# 1-Schematic_RUBBER_DUCKY.net
KiCad netlist of a schematic drawn in EasyEDA
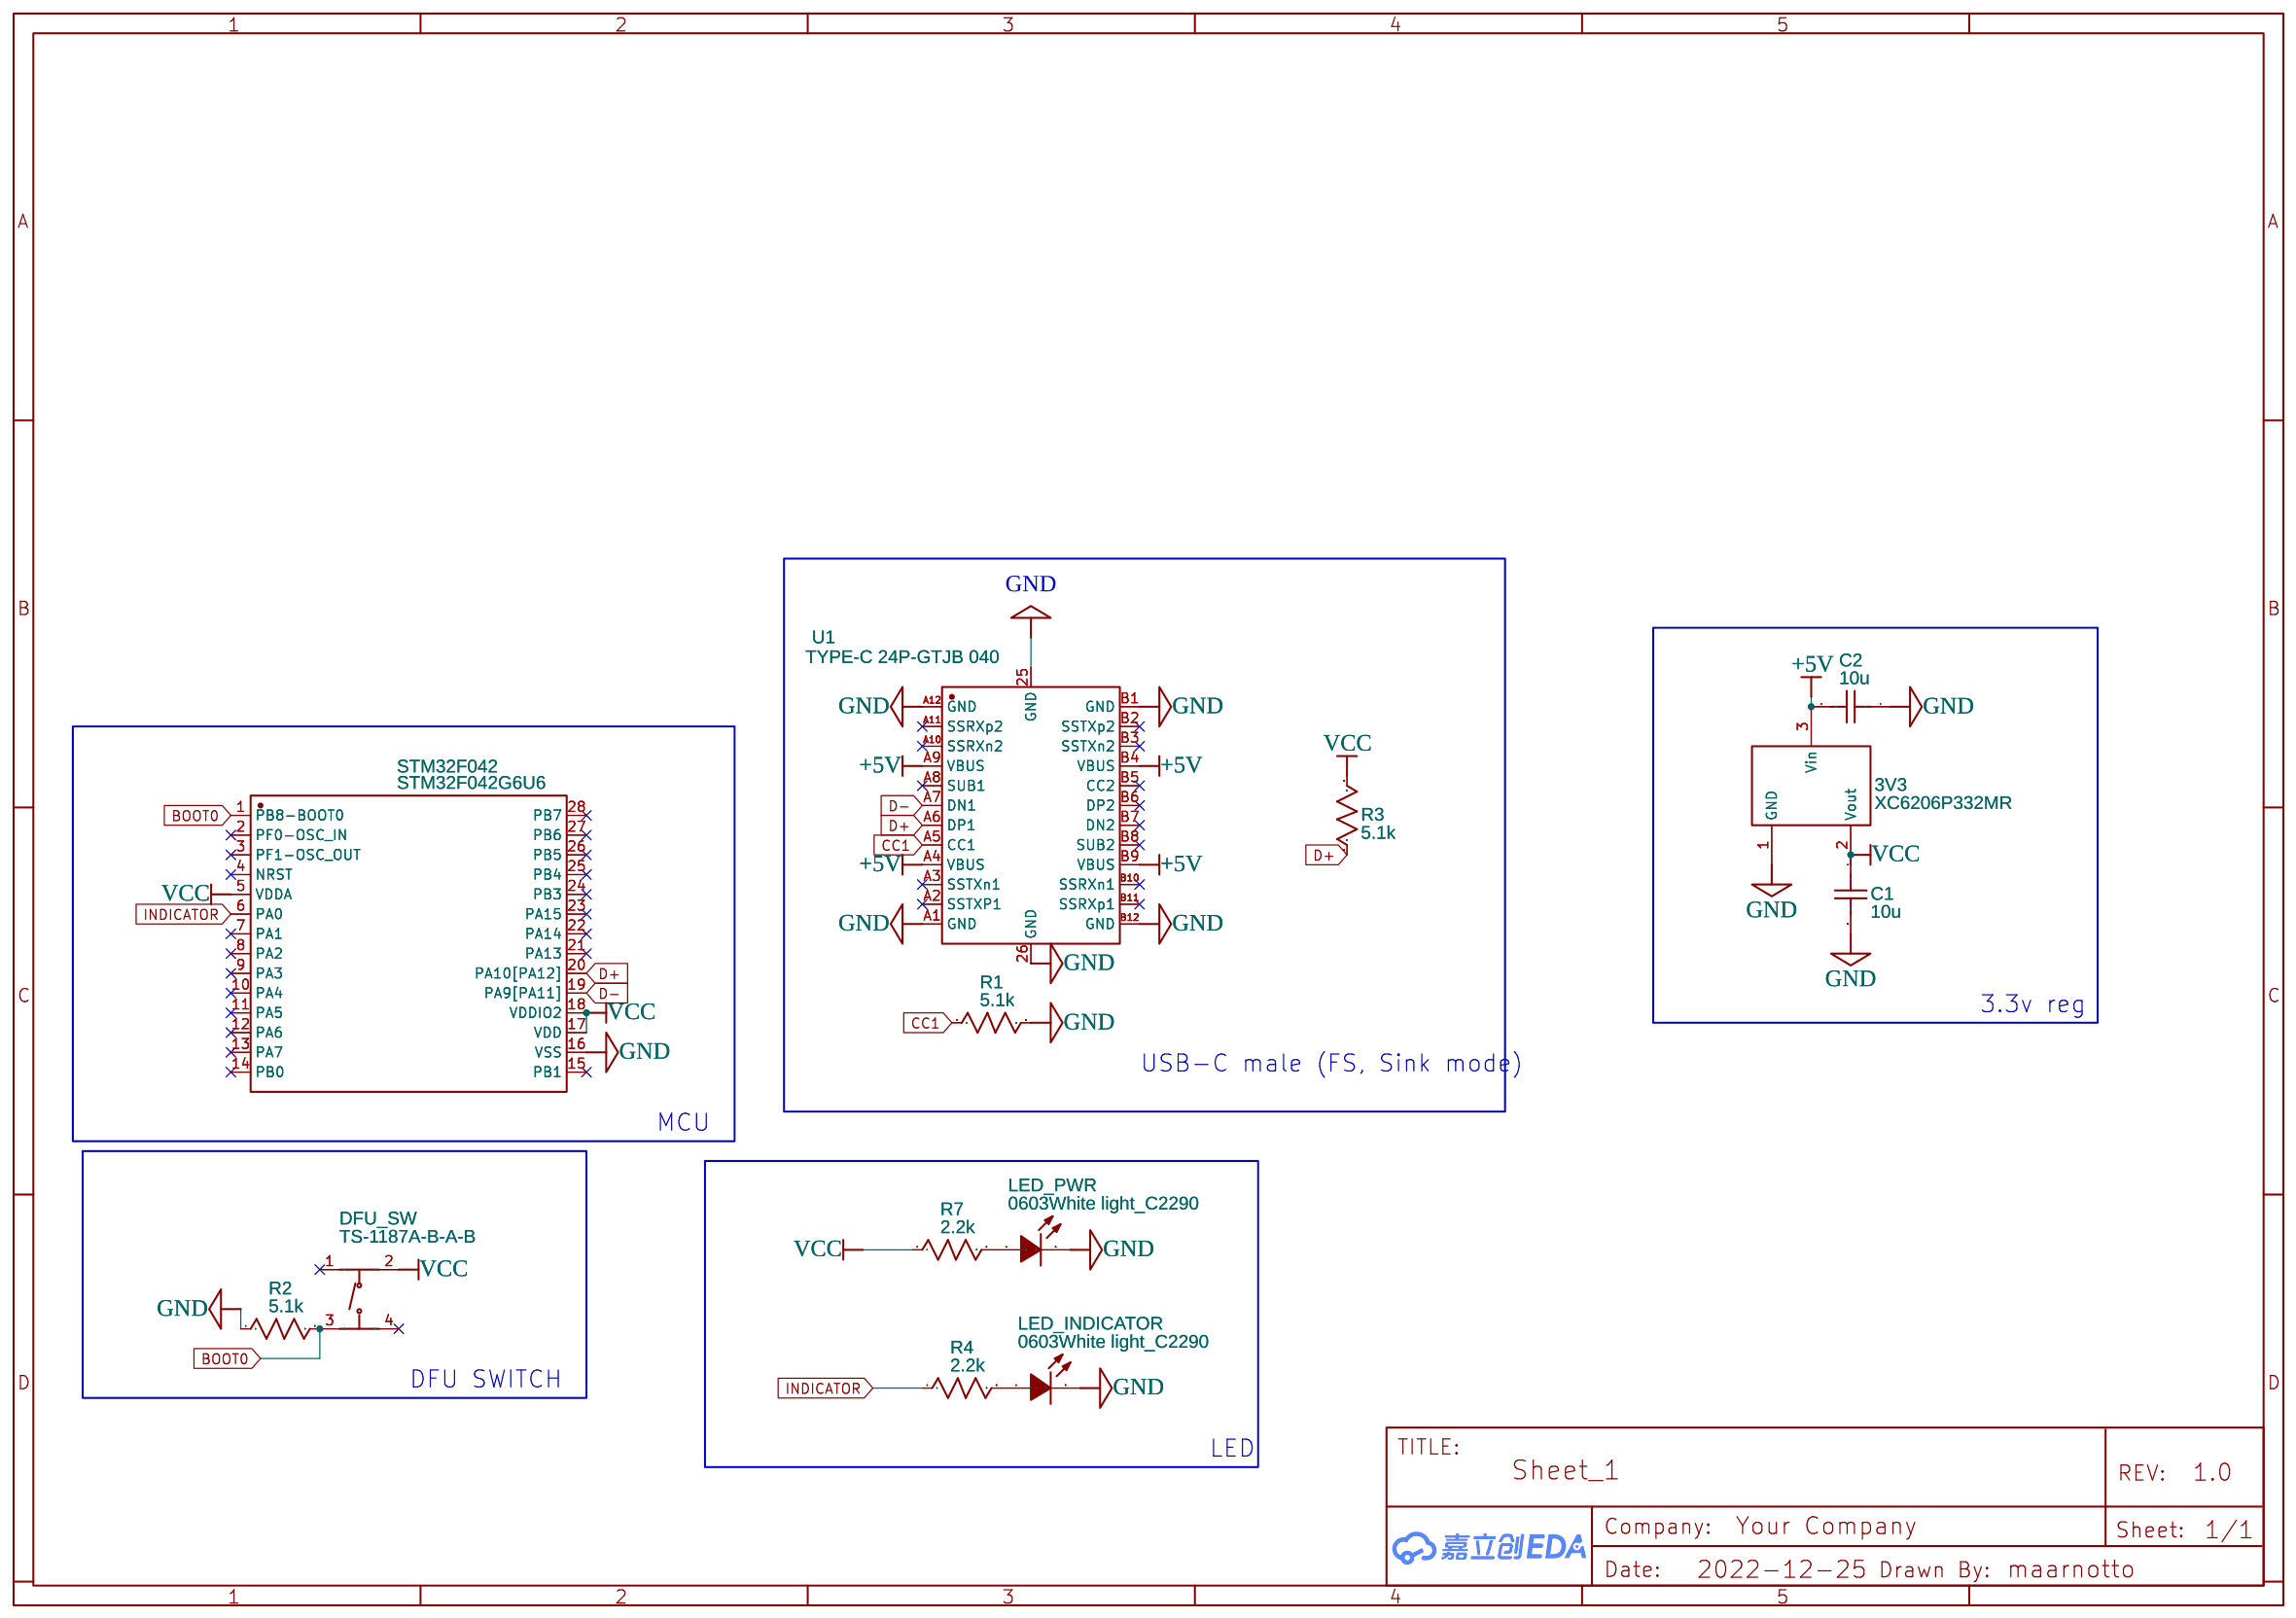
[diagram p0: schematic sheet]

(export (version "E")
  (design (tool "Eeschema 10.0.6"))
  (components
    (comp (ref "3V3")
      (value "XC6206P332MR")
      (fields (field (name "Manufacturer") "TOREX(特瑞仕)"))
      (libsource (lib "") (part "XC6206P332MR"))
    )
    (comp (ref "C1") (value "10u") (libsource (lib "") (part "C_0603_US_1")))
    (comp (ref "C2") (value "10u") (libsource (lib "") (part "C_0603_US")))
    (comp (ref "DFU_SW")
      (value "TS-1187A-B-A-B")
      (fields (field (name "Manufacturer") "XKB Connectivity(中国星坤)"))
      (libsource (lib "") (part "TS-1187A-B-A-B"))
    )
    (comp (ref "LED_INDICATOR")
      (value "0603White light_C2290")
      (fields (field (name "Manufacturer Part") "KT-0603白灯"))
      (libsource (lib "") (part "0603White light_C2290"))
    )
    (comp (ref "LED_PWR")
      (value "0603White light_C2290")
      (fields (field (name "Manufacturer Part") "KT-0603白灯"))
      (libsource (lib "") (part "0603White light_C2290_1"))
    )
    (comp (ref "R1") (value "5.1k") (libsource (lib "") (part "R_0603_US")))
    (comp (ref "R2") (value "5.1k") (libsource (lib "") (part "R_0603_US")))
    (comp (ref "R3") (value "5.1k") (libsource (lib "") (part "R_0603_US_1")))
    (comp (ref "R4") (value "2.2k") (libsource (lib "") (part "R_0603_US")))
    (comp (ref "R7") (value "2.2k") (libsource (lib "") (part "R_0603_US")))
    (comp (ref "STM32F042")
      (value "STM32F042G6U6")
      (fields (field (name "Manufacturer") "ST(意法半导体)"))
      (libsource (lib "") (part "STM32F042G6U6"))
    )
    (comp (ref "U1")
      (value "TYPE-C 24P-GTJB 040")
      (fields (field (name "Manufacturer") "SHOU HAN(首韩)"))
      (libsource (lib "") (part "TYPE-C 24P-GTJB 040"))
    )
  )
  (nets
    (net (code "1") (name "+5V") (class "Default")
      (node (ref "3V3") (pin "3") (pinfunction "Vin_3") (pintype "unspecified"))
      (node (ref "C2") (pin "2") (pinfunction "2_2") (pintype "unspecified"))
      (node (ref "U1") (pin "A4") (pinfunction "VBUS_A4") (pintype "unspecified"))
      (node (ref "U1") (pin "A9") (pinfunction "VBUS_A9") (pintype "unspecified"))
      (node (ref "U1") (pin "B4") (pinfunction "VBUS_B4") (pintype "unspecified"))
      (node (ref "U1") (pin "B9") (pinfunction "VBUS_B9") (pintype "unspecified"))
    )
    (net (code "2") (name "BOOT0") (class "Default")
      (node (ref "DFU_SW") (pin "3") (pinfunction "C_3") (pintype "unspecified"))
      (node (ref "R2") (pin "2") (pinfunction "2_2") (pintype "unspecified"))
      (node (ref "STM32F042") (pin "1") (pinfunction "PB8-BOOT0_1") (pintype "unspecified"))
    )
    (net (code "3") (name "CC1") (class "Default")
      (node (ref "R1") (pin "1") (pinfunction "1_1") (pintype "unspecified"))
      (node (ref "U1") (pin "A5") (pinfunction "CC1_A5") (pintype "unspecified"))
    )
    (net (code "4") (name "D+") (class "Default")
      (node (ref "R3") (pin "2") (pinfunction "2_2") (pintype "unspecified"))
      (node (ref "STM32F042") (pin "20") (pinfunction "PA10[PA12]_20") (pintype "unspecified"))
      (node (ref "U1") (pin "A6") (pinfunction "DP1_A6") (pintype "unspecified"))
    )
    (net (code "5") (name "D-") (class "Default")
      (node (ref "STM32F042") (pin "19") (pinfunction "PA9[PA11]_19") (pintype "unspecified"))
      (node (ref "U1") (pin "A7") (pinfunction "DN1_A7") (pintype "unspecified"))
    )
    (net (code "6") (name "GND") (class "Default")
      (node (ref "3V3") (pin "1") (pinfunction "GND_1") (pintype "unspecified"))
      (node (ref "C1") (pin "2") (pinfunction "2_2") (pintype "unspecified"))
      (node (ref "C2") (pin "1") (pinfunction "1_1") (pintype "unspecified"))
      (node (ref "LED_INDICATOR") (pin "2") (pinfunction "K_2") (pintype "unspecified"))
      (node (ref "LED_PWR") (pin "2") (pinfunction "K_2") (pintype "unspecified"))
      (node (ref "R1") (pin "2") (pinfunction "2_2") (pintype "unspecified"))
      (node (ref "R2") (pin "1") (pinfunction "1_1") (pintype "unspecified"))
      (node (ref "STM32F042") (pin "16") (pinfunction "VSS_16") (pintype "unspecified"))
      (node (ref "U1") (pin "25") (pinfunction "GND_25") (pintype "unspecified"))
      (node (ref "U1") (pin "26") (pinfunction "GND_26") (pintype "unspecified"))
      (node (ref "U1") (pin "A1") (pinfunction "GND_A1") (pintype "unspecified"))
      (node (ref "U1") (pin "A12") (pinfunction "GND_A12") (pintype "unspecified"))
      (node (ref "U1") (pin "B1") (pinfunction "GND_B1") (pintype "unspecified"))
      (node (ref "U1") (pin "B12") (pinfunction "GND_B12") (pintype "unspecified"))
    )
    (net (code "7") (name "INDICATOR") (class "Default")
      (node (ref "R4") (pin "1") (pinfunction "1_1") (pintype "unspecified"))
      (node (ref "STM32F042") (pin "6") (pinfunction "PA0_6") (pintype "unspecified"))
    )
    (net (code "8") (name "Net-(LED_INDICATOR-A)") (class "Default")
      (node (ref "LED_INDICATOR") (pin "1") (pinfunction "A_1") (pintype "unspecified"))
      (node (ref "R4") (pin "2") (pinfunction "2_2") (pintype "unspecified"))
    )
    (net (code "9") (name "Net-(LED_PWR-A)") (class "Default")
      (node (ref "LED_PWR") (pin "1") (pinfunction "A_1") (pintype "unspecified"))
      (node (ref "R7") (pin "2") (pinfunction "2_2") (pintype "unspecified"))
    )
    (net (code "10") (name "VCC") (class "Default")
      (node (ref "3V3") (pin "2") (pinfunction "Vout_2") (pintype "unspecified"))
      (node (ref "C1") (pin "1") (pinfunction "1_1") (pintype "unspecified"))
      (node (ref "DFU_SW") (pin "2") (pinfunction "B_2") (pintype "unspecified"))
      (node (ref "R3") (pin "1") (pinfunction "1_1") (pintype "unspecified"))
      (node (ref "R7") (pin "1") (pinfunction "1_1") (pintype "unspecified"))
      (node (ref "STM32F042") (pin "17") (pinfunction "VDD_17") (pintype "unspecified"))
      (node (ref "STM32F042") (pin "18") (pinfunction "VDDIO2_18") (pintype "unspecified"))
      (node (ref "STM32F042") (pin "5") (pinfunction "VDDA_5") (pintype "unspecified"))
    )
    (net (code "11") (name "unconnected-(DFU_SW-A-Pad1)") (class "Default")
      (node (ref "DFU_SW") (pin "1") (pinfunction "A_1") (pintype "unspecified+no_connect"))
    )
    (net (code "12") (name "unconnected-(DFU_SW-D-Pad4)") (class "Default")
      (node (ref "DFU_SW") (pin "4") (pinfunction "D_4") (pintype "unspecified+no_connect"))
    )
    (net (code "13") (name "unconnected-(STM32F042-NRST-Pad4)") (class "Default")
      (node (ref "STM32F042") (pin "4") (pinfunction "NRST_4") (pintype "unspecified+no_connect"))
    )
    (net (code "14") (name "unconnected-(STM32F042-PA1-Pad7)") (class "Default")
      (node (ref "STM32F042") (pin "7") (pinfunction "PA1_7") (pintype "unspecified+no_connect"))
    )
    (net (code "15") (name "unconnected-(STM32F042-PA2-Pad8)") (class "Default")
      (node (ref "STM32F042") (pin "8") (pinfunction "PA2_8") (pintype "unspecified+no_connect"))
    )
    (net (code "16") (name "unconnected-(STM32F042-PA3-Pad9)") (class "Default")
      (node (ref "STM32F042") (pin "9") (pinfunction "PA3_9") (pintype "unspecified+no_connect"))
    )
    (net (code "17") (name "unconnected-(STM32F042-PA4-Pad10)") (class "Default")
      (node (ref "STM32F042") (pin "10") (pinfunction "PA4_10") (pintype "unspecified+no_connect"))
    )
    (net (code "18") (name "unconnected-(STM32F042-PA5-Pad11)") (class "Default")
      (node (ref "STM32F042") (pin "11") (pinfunction "PA5_11") (pintype "unspecified+no_connect"))
    )
    (net (code "19") (name "unconnected-(STM32F042-PA6-Pad12)") (class "Default")
      (node (ref "STM32F042") (pin "12") (pinfunction "PA6_12") (pintype "unspecified+no_connect"))
    )
    (net (code "20") (name "unconnected-(STM32F042-PA7-Pad13)") (class "Default")
      (node (ref "STM32F042") (pin "13") (pinfunction "PA7_13") (pintype "unspecified+no_connect"))
    )
    (net (code "21") (name "unconnected-(STM32F042-PA13-Pad21)") (class "Default")
      (node (ref "STM32F042") (pin "21") (pinfunction "PA13_21") (pintype "unspecified+no_connect"))
    )
    (net (code "22") (name "unconnected-(STM32F042-PA14-Pad22)") (class "Default")
      (node (ref "STM32F042") (pin "22") (pinfunction "PA14_22") (pintype "unspecified+no_connect"))
    )
    (net (code "23") (name "unconnected-(STM32F042-PA15-Pad23)") (class "Default")
      (node (ref "STM32F042") (pin "23") (pinfunction "PA15_23") (pintype "unspecified+no_connect"))
    )
    (net (code "24") (name "unconnected-(STM32F042-PB0-Pad14)") (class "Default")
      (node (ref "STM32F042") (pin "14") (pinfunction "PB0_14") (pintype "unspecified+no_connect"))
    )
    (net (code "25") (name "unconnected-(STM32F042-PB1-Pad15)") (class "Default")
      (node (ref "STM32F042") (pin "15") (pinfunction "PB1_15") (pintype "unspecified+no_connect"))
    )
    (net (code "26") (name "unconnected-(STM32F042-PB3-Pad24)") (class "Default")
      (node (ref "STM32F042") (pin "24") (pinfunction "PB3_24") (pintype "unspecified+no_connect"))
    )
    (net (code "27") (name "unconnected-(STM32F042-PB4-Pad25)") (class "Default")
      (node (ref "STM32F042") (pin "25") (pinfunction "PB4_25") (pintype "unspecified+no_connect"))
    )
    (net (code "28") (name "unconnected-(STM32F042-PB5-Pad26)") (class "Default")
      (node (ref "STM32F042") (pin "26") (pinfunction "PB5_26") (pintype "unspecified+no_connect"))
    )
    (net (code "29") (name "unconnected-(STM32F042-PB6-Pad27)") (class "Default")
      (node (ref "STM32F042") (pin "27") (pinfunction "PB6_27") (pintype "unspecified+no_connect"))
    )
    (net (code "30") (name "unconnected-(STM32F042-PB7-Pad28)") (class "Default")
      (node (ref "STM32F042") (pin "28") (pinfunction "PB7_28") (pintype "unspecified+no_connect"))
    )
    (net (code "31") (name "unconnected-(STM32F042-PF0-OSC_IN-Pad2)") (class "Default")
      (node (ref "STM32F042") (pin "2") (pinfunction "PF0-OSC_IN_2") (pintype "unspecified+no_connect"))
    )
    (net (code "32") (name "unconnected-(STM32F042-PF1-OSC_OUT-Pad3)") (class "Default")
      (node (ref "STM32F042") (pin "3") (pinfunction "PF1-OSC_OUT_3") (pintype "unspecified+no_connect"))
    )
    (net (code "33") (name "unconnected-(U1-CC2-PadB5)") (class "Default")
      (node (ref "U1") (pin "B5") (pinfunction "CC2_B5") (pintype "unspecified+no_connect"))
    )
    (net (code "34") (name "unconnected-(U1-DN2-PadB7)") (class "Default")
      (node (ref "U1") (pin "B7") (pinfunction "DN2_B7") (pintype "unspecified+no_connect"))
    )
    (net (code "35") (name "unconnected-(U1-DP2-PadB6)") (class "Default")
      (node (ref "U1") (pin "B6") (pinfunction "DP2_B6") (pintype "unspecified+no_connect"))
    )
    (net (code "36") (name "unconnected-(U1-SSRXn1-PadB10)") (class "Default")
      (node (ref "U1") (pin "B10") (pinfunction "SSRXn1_B10") (pintype "unspecified+no_connect"))
    )
    (net (code "37") (name "unconnected-(U1-SSRXn2-PadA10)") (class "Default")
      (node (ref "U1") (pin "A10") (pinfunction "SSRXn2_A10") (pintype "unspecified+no_connect"))
    )
    (net (code "38") (name "unconnected-(U1-SSRXp1-PadB11)") (class "Default")
      (node (ref "U1") (pin "B11") (pinfunction "SSRXp1_B11") (pintype "unspecified+no_connect"))
    )
    (net (code "39") (name "unconnected-(U1-SSRXp2-PadA11)") (class "Default")
      (node (ref "U1") (pin "A11") (pinfunction "SSRXp2_A11") (pintype "unspecified+no_connect"))
    )
    (net (code "40") (name "unconnected-(U1-SSTXP1-PadA2)") (class "Default")
      (node (ref "U1") (pin "A2") (pinfunction "SSTXP1_A2") (pintype "unspecified+no_connect"))
    )
    (net (code "41") (name "unconnected-(U1-SSTXn1-PadA3)") (class "Default")
      (node (ref "U1") (pin "A3") (pinfunction "SSTXn1_A3") (pintype "unspecified+no_connect"))
    )
    (net (code "42") (name "unconnected-(U1-SSTXn2-PadB3)") (class "Default")
      (node (ref "U1") (pin "B3") (pinfunction "SSTXn2_B3") (pintype "unspecified+no_connect"))
    )
    (net (code "43") (name "unconnected-(U1-SSTXp2-PadB2)") (class "Default")
      (node (ref "U1") (pin "B2") (pinfunction "SSTXp2_B2") (pintype "unspecified+no_connect"))
    )
    (net (code "44") (name "unconnected-(U1-SUB1-PadA8)") (class "Default")
      (node (ref "U1") (pin "A8") (pinfunction "SUB1_A8") (pintype "unspecified+no_connect"))
    )
    (net (code "45") (name "unconnected-(U1-SUB2-PadB8)") (class "Default")
      (node (ref "U1") (pin "B8") (pinfunction "SUB2_B8") (pintype "unspecified+no_connect"))
    )
  )
)
